# STM32F407VGT6TR_100P_MCU.net
KiCad netlist of a schematic drawn in Altium Designer
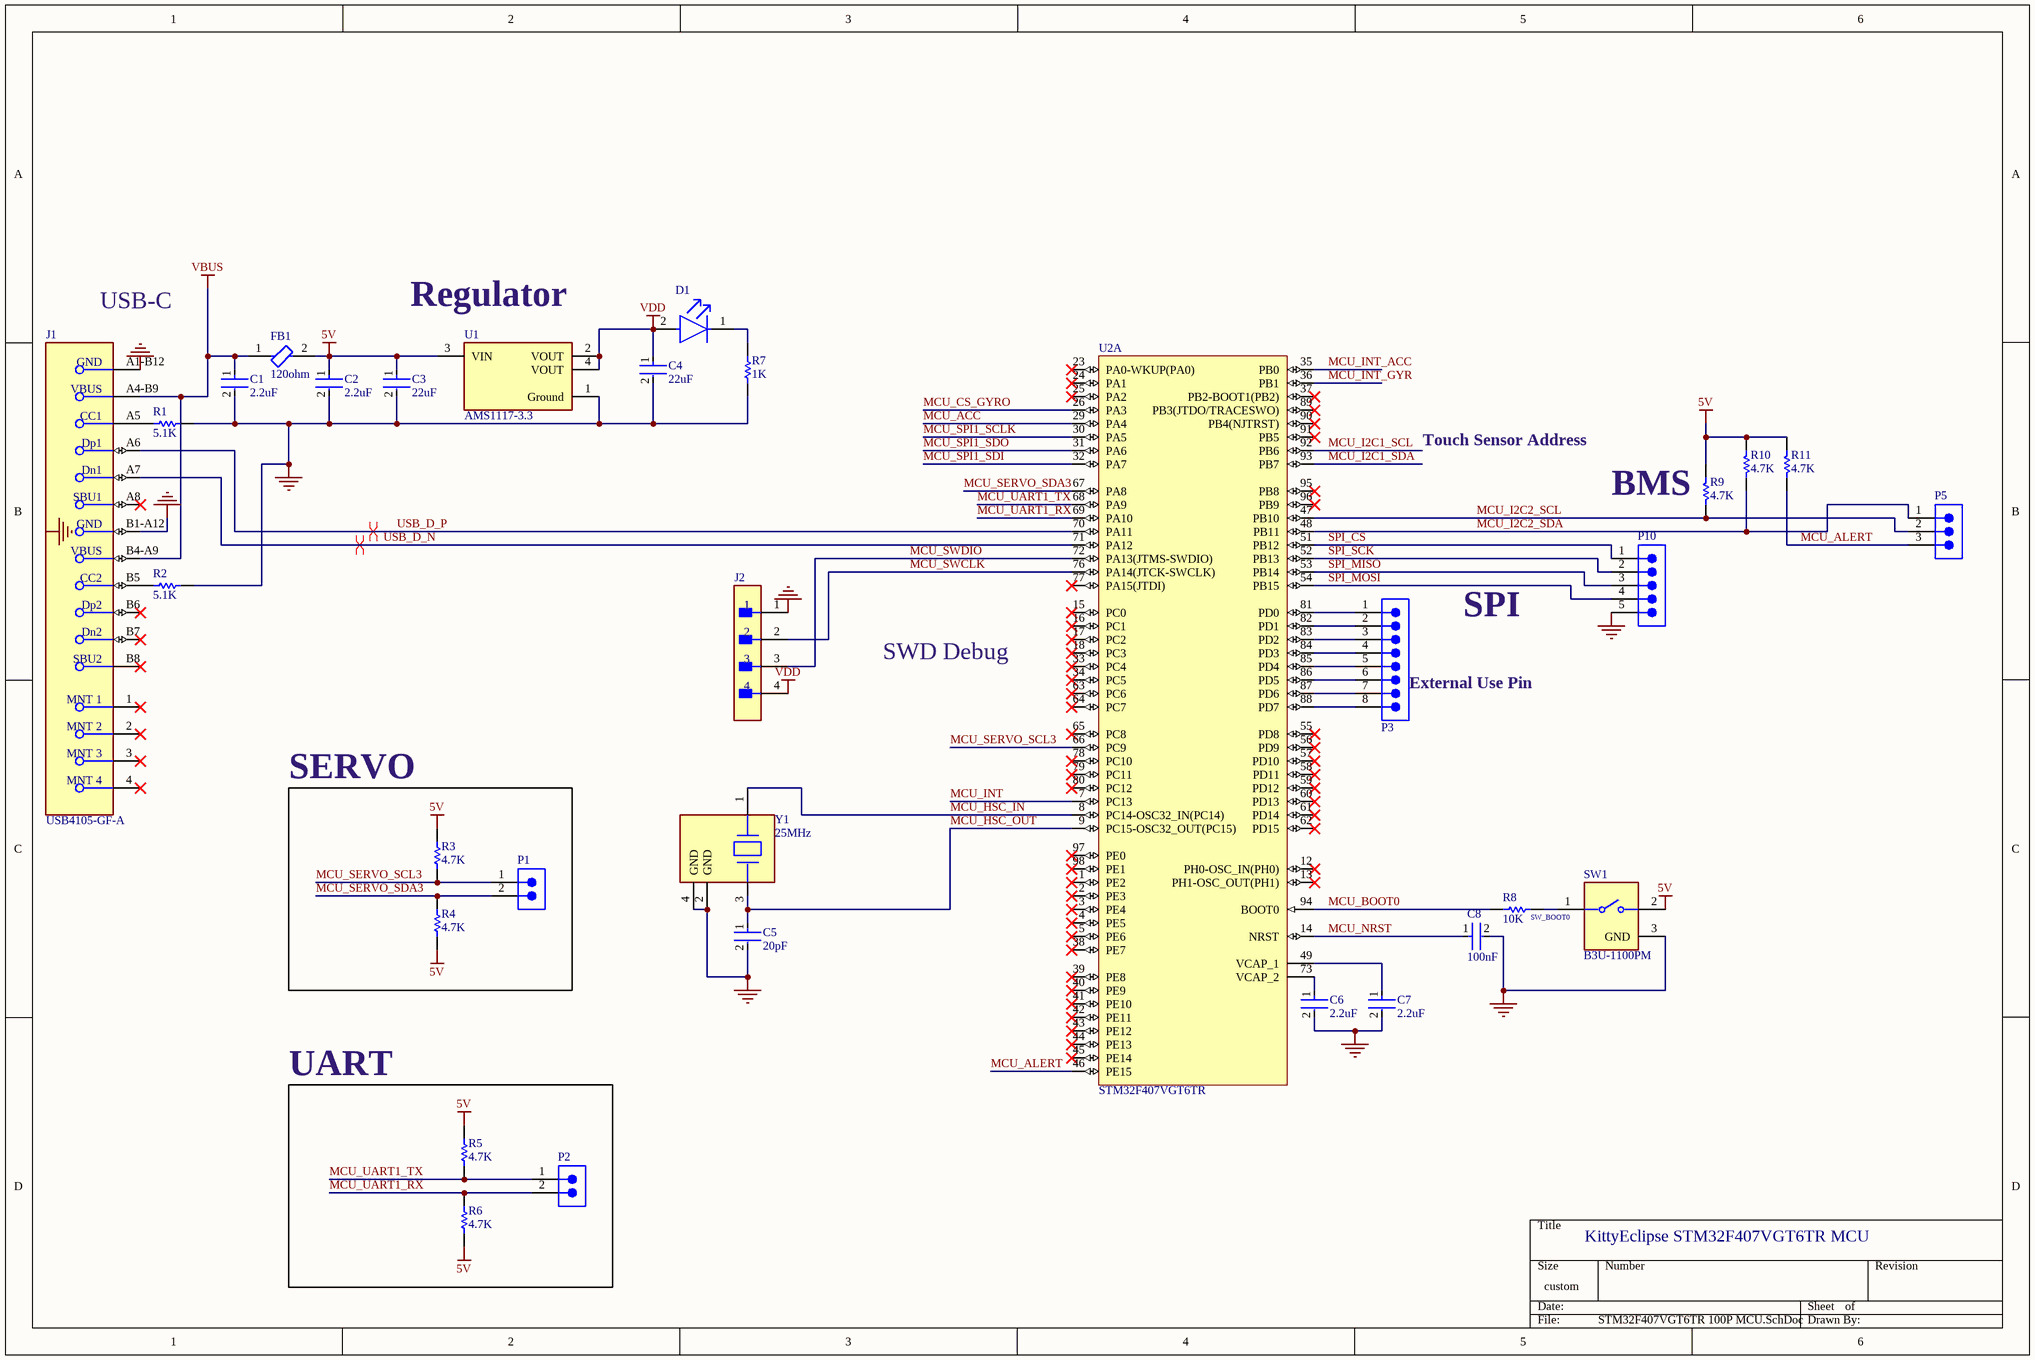
[diagram p0: STM32F407VGT6TR 100P MCU.SchDoc]

(export (version "E")
  (design (tool "Eeschema 10.0.6"))
  (components
    (comp (ref "C1")
      (value "2.2uF")
      (footprint "FP-CL10-IPC_A")
      (description "Cap Ceramic 2.2uF 16V X5R ±10% Pad SMD 0603 +85°C T/R")
      (fields (field (name "TOLERANCE") "10%") (field (name "VOLTAGE") "16V"))
      (libsource (lib "Altium Content Vault") (part "b4654b650e69147ec39a6b967a45e02"))
    )
    (comp (ref "C2")
      (value "2.2uF")
      (footprint "FP-CL10-IPC_A")
      (description "Cap Ceramic 2.2uF 16V X5R ±10% Pad SMD 0603 +85°C T/R")
      (fields (field (name "TOLERANCE") "10%") (field (name "VOLTAGE") "16V"))
      (libsource (lib "Altium Content Vault") (part "b4654b650e69147ec39a6b967a45e02"))
    )
    (comp (ref "C3")
      (value "22uF")
      (footprint "FP-CL21-IPC_A")
      (description "CL21 Series 0805 22uF 6.3V ±20% Tolerance X5R Multilayer Ceramic Chip Capacitor")
      (fields (field (name "TOLERANCE") "20%"))
      (libsource (lib "Altium Content Vault") (part "b4654b650e69147ec39a6b967a45e02"))
    )
    (comp (ref "C4")
      (value "22uF")
      (footprint "FP-CL21-IPC_A")
      (description "CL21 Series 0805 22uF 6.3V ±20% Tolerance X5R Multilayer Ceramic Chip Capacitor")
      (fields (field (name "TOLERANCE") "20%"))
      (libsource (lib "Altium Content Vault") (part "b4654b650e69147ec39a6b967a45e02"))
    )
    (comp (ref "C5")
      (value "20pF")
      (footprint "FP-GCM155-0_05-IPC_A")
      (description "Ceramic Capacitor for Automotive 220pF ±5% 50VDC C0G 0402 Paper T/R")
      (fields (field (name "VOLTAGE") "50V") (field (name "TOLERANCE") "5%"))
      (libsource (lib "Altium Content Vault") (part "02cd4be3c70576c341d710602a673aa"))
    )
    (comp (ref "C6")
      (value "2.2uF")
      (footprint "FP-CL10-IPC_A")
      (description "Cap Ceramic 2.2uF 16V X5R ±10% Pad SMD 0603 +85°C T/R")
      (fields (field (name "TOLERANCE") "10%") (field (name "VOLTAGE") "16V"))
      (libsource (lib "Altium Content Vault") (part "b4654b650e69147ec39a6b967a45e02"))
    )
    (comp (ref "C7")
      (value "2.2uF")
      (footprint "FP-CL10-IPC_A")
      (description "Cap Ceramic 2.2uF 16V X5R ±10% Pad SMD 0603 +85°C T/R")
      (fields (field (name "TOLERANCE") "10%") (field (name "VOLTAGE") "16V"))
      (libsource (lib "Altium Content Vault") (part "b4654b650e69147ec39a6b967a45e02"))
    )
    (comp (ref "C8")
      (value "100nF")
      (footprint "FP-CL93-IPC_C")
      (description "Cap Ceramic 100nF 10V X7R ±10% SMD 0402 +125°C Paper T/R")
      (libsource (lib "Altium Content Vault") (part "b4654b650e69147ec39a6b967a45e02"))
    )
    (comp (ref "D1")
      (value "LTST-C190GKT")
      (footprint "FP-LTST-C190GKT-MFG")
      (description "LED GREEN CLEAR CHIP SMD")
      (fields (field (name "VOLTAGE") "2V"))
      (libsource (lib "Altium Content Vault") (part "8706943c75ba83719d021d2fdc84c58"))
    )
    (comp (ref "FB1")
      (value "120ohm")
      (footprint "FP-MPZ1608-0_8-IPC_C")
      (description "Power line Ferrite Bead 390Ω @ 100MHz 1.2A DCR 0.12Ω SMD 0603")
      (fields (field (name "TOLERANCE") "25%"))
      (libsource (lib "Altium Content Vault") (part "5f30dd21d616792df468990f7003faa"))
    )
    (comp (ref "J1")
      (value "USB4105-GF-A")
      (footprint "FP-USB4105-GF-A-MFG")
      (description "CONN RCPT USB2.0 TYPEC 5A")
      (fields
        (field (name "MANUFACTURER") "GCT")
        (field (name "OCTOPART") "https://octopart.com/usb4105-gf-a-gct-106627878")
      )
      (libsource (lib "Altium Content Vault") (part "e7c17a616881a82b79941196b4bec10"))
    )
    (comp (ref "J2")
      (value "B4B-ZR(LF)(SN)")
      (footprint "FP-B4B-ZR_LF_SN-MFG")
      (description "CONN HEADER VERT 4POS 1.5MM")
      (libsource (lib "Altium Content Vault") (part "299a8cea1bdcbc3624fe62c390fa72c"))
    )
    (comp (ref "P1")
      (value "61300211121")
      (footprint "61300211121")
      (libsource (lib "Altium Content Vault") (part "Header_Male_1R_02P"))
    )
    (comp (ref "P2")
      (value "61300211121")
      (footprint "61300211121")
      (libsource (lib "Altium Content Vault") (part "Header_Male_1R_02P"))
    )
    (comp (ref "P3")
      (value "61300811121")
      (footprint "61300811121")
      (libsource (lib "Altium Content Vault") (part "Header_Male_1R_08P"))
    )
    (comp (ref "P5")
      (value "61300311121")
      (footprint "61300311121")
      (libsource (lib "Altium Content Vault") (part "Header_Male_1R_03P"))
    )
    (comp (ref "P10")
      (value "61300511121")
      (footprint "61300511121")
      (libsource (lib "Altium Content Vault") (part "Header_Male_1R_05P"))
    )
    (comp (ref "R1")
      (value "5.1K")
      (footprint "RESC1005X40X25NL10T10")
      (fields (field (name "MANUFACTURER") "Panasonic") (field (name "PART NUMBER") "ERA-2AEB512X"))
      (libsource (lib "Altium Content Vault") (part "RES"))
    )
    (comp (ref "R2")
      (value "5.1K")
      (footprint "RESC1005X40X25NL10T10")
      (fields (field (name "MANUFACTURER") "Panasonic") (field (name "PART NUMBER") "ERA-2AEB512X"))
      (libsource (lib "Altium Content Vault") (part "RES"))
    )
    (comp (ref "R3")
      (value "4.7K")
      (footprint "RESC1608X55X25LL10T15")
      (description "Chip Resistor, 4.7 KOhm, +/- 1%, 0.1 W, -55 to 155 degC, 0603 (1608 Metric), RoHS, Tape and Reel")
      (fields (field (name "MANUFACTURER") "Yageo") (field (name "TOLERANCE") "1%"))
      (libsource (lib "Altium Content Vault") (part "RES-2"))
    )
    (comp (ref "R4")
      (value "4.7K")
      (footprint "RESC1608X55X25LL10T15")
      (description "Chip Resistor, 4.7 KOhm, +/- 1%, 0.1 W, -55 to 155 degC, 0603 (1608 Metric), RoHS, Tape and Reel")
      (fields (field (name "MANUFACTURER") "Yageo") (field (name "TOLERANCE") "1%"))
      (libsource (lib "Altium Content Vault") (part "RES-2"))
    )
    (comp (ref "R5")
      (value "4.7K")
      (footprint "RESC1608X55X25LL10T15")
      (description "Chip Resistor, 4.7 KOhm, +/- 1%, 0.1 W, -55 to 155 degC, 0603 (1608 Metric), RoHS, Tape and Reel")
      (fields (field (name "MANUFACTURER") "Yageo") (field (name "TOLERANCE") "1%"))
      (libsource (lib "Altium Content Vault") (part "RES-2"))
    )
    (comp (ref "R6")
      (value "4.7K")
      (footprint "RESC1608X55X25LL10T15")
      (description "Chip Resistor, 4.7 KOhm, +/- 1%, 0.1 W, -55 to 155 degC, 0603 (1608 Metric), RoHS, Tape and Reel")
      (fields (field (name "MANUFACTURER") "Yageo") (field (name "TOLERANCE") "1%"))
      (libsource (lib "Altium Content Vault") (part "RES-2"))
    )
    (comp (ref "R7")
      (value "1K")
      (footprint "RESC1608X55X30LL15T15")
      (fields (field (name "PART NUMBER") "ERJ-3EKF1001V") (field (name "MANUFACTURER") "Panasonic"))
      (libsource (lib "Altium Content Vault") (part "RES"))
    )
    (comp (ref "R8")
      (value "10K")
      (footprint "RESC1608X55X25ML10T15")
      (description "Resistor, 10 KOhm, +/- 5%, 100 mW, -55 to 155 degC, 0603 (1608 Metric), RoHS, Tape and Reel")
      (fields (field (name "MANUFACTURER") "Yageo") (field (name "TOLERANCE") "5%"))
      (libsource (lib "Altium Content Vault") (part "RES-2"))
    )
    (comp (ref "R9")
      (value "4.7K")
      (footprint "RESC1608X55X25LL10T15")
      (description "Chip Resistor, 4.7 KOhm, +/- 1%, 0.1 W, -55 to 155 degC, 0603 (1608 Metric), RoHS, Tape and Reel")
      (fields (field (name "MANUFACTURER") "Yageo") (field (name "TOLERANCE") "1%"))
      (libsource (lib "Altium Content Vault") (part "RES-2"))
    )
    (comp (ref "R10")
      (value "4.7K")
      (footprint "RESC1608X55X25LL10T15")
      (description "Chip Resistor, 4.7 KOhm, +/- 1%, 0.1 W, -55 to 155 degC, 0603 (1608 Metric), RoHS, Tape and Reel")
      (fields (field (name "MANUFACTURER") "Yageo") (field (name "TOLERANCE") "1%"))
      (libsource (lib "Altium Content Vault") (part "RES-2"))
    )
    (comp (ref "R11")
      (value "4.7K")
      (footprint "RESC1608X55X25LL10T15")
      (description "Chip Resistor, 4.7 KOhm, +/- 1%, 0.1 W, -55 to 155 degC, 0603 (1608 Metric), RoHS, Tape and Reel")
      (fields (field (name "MANUFACTURER") "Yageo") (field (name "TOLERANCE") "1%"))
      (libsource (lib "Altium Content Vault") (part "RES-2"))
    )
    (comp (ref "SW1")
      (value "B3U-1100PM")
      (footprint "FP-B3U-1100PM-MFG")
      (description "SWITCH TACTILE SPST-NO 0.05A 12V")
      (libsource (lib "Altium Content Vault") (part "6d7322ea62e06c21cb959ab9578dfa0"))
    )
    (comp (ref "U1")
      (value "AMS1117-3.3")
      (footprint "FP-AMS1117-IPC_C")
      (description "LDO Voltage Regulators 1A, 3.3V")
      (fields
        (field (name "OCTOPART") "https://octopart.com/ams1117-3.3-advanced+monolithic+systems-25899300")
        (field (name "MANUFACTURER") "Advanced Monolithic Systems")
      )
      (libsource (lib "Altium Content Vault") (part "8bdbb5f8e77002000e30dd2845d0354"))
    )
    (comp (ref "U2")
      (value "STM32F407VGT6TR")
      (footprint "STM-LQFP100_L")
      (fields (field (name "MANUFACTURER") "STMicroelectronics"))
      (libsource (lib "Altium Content Vault") (part "MC-ARM-STM32F40X_41X-SQ100"))
    )
    (comp (ref "Y1")
      (value "25MHz")
      (footprint "FP-ABM11W-MFG")
      (description "Crystal 25MHz ±10ppm 8pF SMD-4 2mm x 1.6mm")
      (libsource (lib "Altium Content Vault") (part "5fba445d8d5f95165d6b3865099b029"))
    )
  )
  (nets
    (net (code "1") (name "/MCU_ACC") (class "Default")
      (node (ref "U2") (pin "29") (pinfunction "PA4_29") (pintype "bidirectional"))
    )
    (net (code "2") (name "/MCU_ALERT") (class "Default")
      (node (ref "P5") (pin "3") (pinfunction "3_3") (pintype "passive"))
      (node (ref "R11") (pin "2") (pinfunction "2_2") (pintype "passive"))
      (node (ref "U2") (pin "46") (pinfunction "PE15_46") (pintype "bidirectional"))
    )
    (net (code "3") (name "/MCU_BOOT0") (class "Default")
      (node (ref "R8") (pin "1") (pinfunction "1_1") (pintype "passive"))
      (node (ref "U2") (pin "94") (pinfunction "BOOT0_94") (pintype "input"))
    )
    (net (code "4") (name "/MCU_CS_GYRO") (class "Default")
      (node (ref "U2") (pin "26") (pinfunction "PA3_26") (pintype "bidirectional"))
    )
    (net (code "5") (name "/MCU_HSC_IN") (class "Default")
      (node (ref "U2") (pin "8") (pinfunction "PC14-OSC32_IN(PC14)_8") (pintype "bidirectional"))
      (node (ref "Y1") (pin "1") (pinfunction "1_1") (pintype "passive"))
    )
    (net (code "6") (name "/MCU_HSC_OUT") (class "Default")
      (node (ref "C5") (pin "1") (pinfunction "1_1") (pintype "passive"))
      (node (ref "U2") (pin "9") (pinfunction "PC15-OSC32_OUT(PC15)_9") (pintype "bidirectional"))
      (node (ref "Y1") (pin "3") (pinfunction "3_3") (pintype "passive"))
    )
    (net (code "7") (name "/MCU_I2C1_SCL") (class "Default")
      (node (ref "U2") (pin "92") (pinfunction "PB6_92") (pintype "bidirectional"))
    )
    (net (code "8") (name "/MCU_I2C1_SDA") (class "Default")
      (node (ref "U2") (pin "93") (pinfunction "PB7_93") (pintype "bidirectional"))
    )
    (net (code "9") (name "/MCU_I2C2_SCL") (class "Default")
      (node (ref "P5") (pin "2") (pinfunction "2_2") (pintype "passive"))
      (node (ref "R9") (pin "2") (pinfunction "2_2") (pintype "passive"))
      (node (ref "U2") (pin "47") (pinfunction "PB10_47") (pintype "bidirectional"))
    )
    (net (code "10") (name "/MCU_I2C2_SDA") (class "Default")
      (node (ref "P5") (pin "1") (pinfunction "1_1") (pintype "passive"))
      (node (ref "R10") (pin "2") (pinfunction "2_2") (pintype "passive"))
      (node (ref "U2") (pin "48") (pinfunction "PB11_48") (pintype "bidirectional"))
    )
    (net (code "11") (name "/MCU_INT") (class "Default")
      (node (ref "U2") (pin "7") (pinfunction "PC13_7") (pintype "bidirectional"))
    )
    (net (code "12") (name "/MCU_INT_ACC") (class "Default")
      (node (ref "U2") (pin "35") (pinfunction "PB0_35") (pintype "bidirectional"))
    )
    (net (code "13") (name "/MCU_INT_GYR") (class "Default")
      (node (ref "U2") (pin "36") (pinfunction "PB1_36") (pintype "bidirectional"))
    )
    (net (code "14") (name "/MCU_NRST") (class "Default")
      (node (ref "C8") (pin "1") (pinfunction "1_1") (pintype "passive"))
      (node (ref "U2") (pin "14") (pinfunction "NRST_14") (pintype "bidirectional"))
    )
    (net (code "15") (name "/MCU_SERVO_SCL3") (class "Default")
      (node (ref "P1") (pin "1") (pinfunction "1_1") (pintype "passive"))
      (node (ref "R3") (pin "1") (pinfunction "1_1") (pintype "passive"))
      (node (ref "U2") (pin "66") (pinfunction "PC9_66") (pintype "bidirectional"))
    )
    (net (code "16") (name "/MCU_SERVO_SDA3") (class "Default")
      (node (ref "P1") (pin "2") (pinfunction "2_2") (pintype "passive"))
      (node (ref "R4") (pin "2") (pinfunction "2_2") (pintype "passive"))
      (node (ref "U2") (pin "67") (pinfunction "PA8_67") (pintype "bidirectional"))
    )
    (net (code "17") (name "/MCU_SPI1_SCLK") (class "Default")
      (node (ref "U2") (pin "30") (pinfunction "PA5_30") (pintype "bidirectional"))
    )
    (net (code "18") (name "/MCU_SPI1_SDI") (class "Default")
      (node (ref "U2") (pin "32") (pinfunction "PA7_32") (pintype "bidirectional"))
    )
    (net (code "19") (name "/MCU_SPI1_SDO") (class "Default")
      (node (ref "U2") (pin "31") (pinfunction "PA6_31") (pintype "bidirectional"))
    )
    (net (code "20") (name "/MCU_SWCLK") (class "Default")
      (node (ref "J2") (pin "2") (pinfunction "2_2") (pintype "passive"))
      (node (ref "U2") (pin "76") (pinfunction "PA14(JTCK-SWCLK)_76") (pintype "bidirectional"))
    )
    (net (code "21") (name "/MCU_SWDIO") (class "Default")
      (node (ref "J2") (pin "3") (pinfunction "3_3") (pintype "passive"))
      (node (ref "U2") (pin "72") (pinfunction "PA13(JTMS-SWDIO)_72") (pintype "bidirectional"))
    )
    (net (code "22") (name "/MCU_UART1_RX") (class "Default")
      (node (ref "P2") (pin "2") (pinfunction "2_2") (pintype "passive"))
      (node (ref "R6") (pin "2") (pinfunction "2_2") (pintype "passive"))
      (node (ref "U2") (pin "69") (pinfunction "PA10_69") (pintype "bidirectional"))
    )
    (net (code "23") (name "/MCU_UART1_TX") (class "Default")
      (node (ref "P2") (pin "1") (pinfunction "1_1") (pintype "passive"))
      (node (ref "R5") (pin "2") (pinfunction "2_2") (pintype "passive"))
      (node (ref "U2") (pin "68") (pinfunction "PA9_68") (pintype "bidirectional"))
    )
    (net (code "24") (name "/SPI_CS") (class "Default")
      (node (ref "P10") (pin "1") (pinfunction "1_1") (pintype "passive"))
      (node (ref "U2") (pin "51") (pinfunction "PB12_51") (pintype "bidirectional"))
    )
    (net (code "25") (name "/SPI_MISO") (class "Default")
      (node (ref "P10") (pin "3") (pinfunction "3_3") (pintype "passive"))
      (node (ref "U2") (pin "53") (pinfunction "PB14_53") (pintype "bidirectional"))
    )
    (net (code "26") (name "/SPI_MOSI") (class "Default")
      (node (ref "P10") (pin "4") (pinfunction "4_4") (pintype "passive"))
      (node (ref "U2") (pin "54") (pinfunction "PB15_54") (pintype "bidirectional"))
    )
    (net (code "27") (name "/SPI_SCK") (class "Default")
      (node (ref "P10") (pin "2") (pinfunction "2_2") (pintype "passive"))
      (node (ref "U2") (pin "52") (pinfunction "PB13_52") (pintype "bidirectional"))
    )
    (net (code "28") (name "/USB_D_N") (class "Default")
      (node (ref "J1") (pin "A7") (pinfunction "Dn1_A7") (pintype "bidirectional"))
      (node (ref "U2") (pin "71") (pinfunction "PA12_71") (pintype "bidirectional"))
    )
    (net (code "29") (name "/USB_D_P") (class "Default")
      (node (ref "J1") (pin "A6") (pinfunction "Dp1_A6") (pintype "bidirectional"))
      (node (ref "U2") (pin "70") (pinfunction "PA11_70") (pintype "bidirectional"))
    )
    (net (code "30") (name "5V") (class "Default")
      (node (ref "C2") (pin "1") (pinfunction "1_1") (pintype "passive"))
      (node (ref "C3") (pin "1") (pinfunction "1_1") (pintype "passive"))
      (node (ref "FB1") (pin "2") (pinfunction "2_2") (pintype "passive"))
      (node (ref "R10") (pin "1") (pinfunction "1_1") (pintype "passive"))
      (node (ref "R11") (pin "1") (pinfunction "1_1") (pintype "passive"))
      (node (ref "R3") (pin "2") (pinfunction "2_2") (pintype "passive"))
      (node (ref "R4") (pin "1") (pinfunction "1_1") (pintype "passive"))
      (node (ref "R5") (pin "1") (pinfunction "1_1") (pintype "passive"))
      (node (ref "R6") (pin "1") (pinfunction "1_1") (pintype "passive"))
      (node (ref "R9") (pin "1") (pinfunction "1_1") (pintype "passive"))
      (node (ref "SW1") (pin "2") (pinfunction "2_2") (pintype "passive"))
      (node (ref "U1") (pin "3") (pinfunction "VIN_3") (pintype "power_in"))
    )
    (net (code "31") (name "GND") (class "Default")
      (node (ref "C1") (pin "2") (pinfunction "2_2") (pintype "passive"))
      (node (ref "C2") (pin "2") (pinfunction "2_2") (pintype "passive"))
      (node (ref "C3") (pin "2") (pinfunction "2_2") (pintype "passive"))
      (node (ref "C4") (pin "2") (pinfunction "2_2") (pintype "passive"))
      (node (ref "C5") (pin "2") (pinfunction "2_2") (pintype "passive"))
      (node (ref "C6") (pin "2") (pinfunction "2_2") (pintype "passive"))
      (node (ref "C7") (pin "2") (pinfunction "2_2") (pintype "passive"))
      (node (ref "C8") (pin "2") (pinfunction "2_2") (pintype "passive"))
      (node (ref "J1") (pin "A1-B12") (pinfunction "GND_A1-B12") (pintype "power_in"))
      (node (ref "J1") (pin "B1-A12") (pinfunction "GND_B1-A12") (pintype "bidirectional"))
      (node (ref "J2") (pin "1") (pinfunction "1_1") (pintype "passive"))
      (node (ref "P10") (pin "5") (pinfunction "5_5") (pintype "passive"))
      (node (ref "R1") (pin "2") (pinfunction "2_2") (pintype "passive"))
      (node (ref "R2") (pin "2") (pinfunction "2_2") (pintype "passive"))
      (node (ref "R7") (pin "2") (pinfunction "2_2") (pintype "passive"))
      (node (ref "SW1") (pin "3") (pinfunction "GND_3") (pintype "power_in"))
      (node (ref "U1") (pin "1") (pinfunction "Ground_1") (pintype "power_in"))
      (node (ref "Y1") (pin "2") (pinfunction "GND_2") (pintype "power_in"))
      (node (ref "Y1") (pin "4") (pinfunction "GND_4") (pintype "power_in"))
    )
    (net (code "32") (name "Net-(D1-C)") (class "Default")
      (node (ref "D1") (pin "1") (pinfunction "C_1") (pintype "passive"))
      (node (ref "R7") (pin "1") (pinfunction "1_1") (pintype "passive"))
    )
    (net (code "33") (name "Net-(J1-CC1)") (class "Default")
      (node (ref "J1") (pin "A5") (pinfunction "CC1_A5") (pintype "power_in"))
      (node (ref "R1") (pin "1") (pinfunction "1_1") (pintype "passive"))
    )
    (net (code "34") (name "Net-(J1-CC2)") (class "Default")
      (node (ref "J1") (pin "B5") (pinfunction "CC2_B5") (pintype "bidirectional"))
      (node (ref "R2") (pin "1") (pinfunction "1_1") (pintype "passive"))
    )
    (net (code "35") (name "Net-(R8-Pad2)") (class "Default")
      (node (ref "R8") (pin "2") (pinfunction "2_2") (pintype "passive"))
      (node (ref "SW1") (pin "1") (pinfunction "1_1") (pintype "passive"))
    )
    (net (code "36") (name "Net-(U2A-PD0)") (class "Default")
      (node (ref "P3") (pin "1") (pinfunction "1_1") (pintype "passive"))
      (node (ref "U2") (pin "81") (pinfunction "PD0_81") (pintype "bidirectional"))
    )
    (net (code "37") (name "Net-(U2A-PD1)") (class "Default")
      (node (ref "P3") (pin "2") (pinfunction "2_2") (pintype "passive"))
      (node (ref "U2") (pin "82") (pinfunction "PD1_82") (pintype "bidirectional"))
    )
    (net (code "38") (name "Net-(U2A-PD2)") (class "Default")
      (node (ref "P3") (pin "3") (pinfunction "3_3") (pintype "passive"))
      (node (ref "U2") (pin "83") (pinfunction "PD2_83") (pintype "bidirectional"))
    )
    (net (code "39") (name "Net-(U2A-PD3)") (class "Default")
      (node (ref "P3") (pin "4") (pinfunction "4_4") (pintype "passive"))
      (node (ref "U2") (pin "84") (pinfunction "PD3_84") (pintype "bidirectional"))
    )
    (net (code "40") (name "Net-(U2A-PD4)") (class "Default")
      (node (ref "P3") (pin "5") (pinfunction "5_5") (pintype "passive"))
      (node (ref "U2") (pin "85") (pinfunction "PD4_85") (pintype "bidirectional"))
    )
    (net (code "41") (name "Net-(U2A-PD5)") (class "Default")
      (node (ref "P3") (pin "6") (pinfunction "6_6") (pintype "passive"))
      (node (ref "U2") (pin "86") (pinfunction "PD5_86") (pintype "bidirectional"))
    )
    (net (code "42") (name "Net-(U2A-PD6)") (class "Default")
      (node (ref "P3") (pin "7") (pinfunction "7_7") (pintype "passive"))
      (node (ref "U2") (pin "87") (pinfunction "PD6_87") (pintype "bidirectional"))
    )
    (net (code "43") (name "Net-(U2A-PD7)") (class "Default")
      (node (ref "P3") (pin "8") (pinfunction "8_8") (pintype "passive"))
      (node (ref "U2") (pin "88") (pinfunction "PD7_88") (pintype "bidirectional"))
    )
    (net (code "44") (name "Net-(U2A-VCAP_1)") (class "Default")
      (node (ref "C7") (pin "1") (pinfunction "1_1") (pintype "passive"))
      (node (ref "U2") (pin "49") (pinfunction "VCAP_1_49") (pintype "power_in"))
    )
    (net (code "45") (name "Net-(U2A-VCAP_2)") (class "Default")
      (node (ref "C6") (pin "1") (pinfunction "1_1") (pintype "passive"))
      (node (ref "U2") (pin "73") (pinfunction "VCAP_2_73") (pintype "power_in"))
    )
    (net (code "46") (name "VBUS") (class "Default")
      (node (ref "C1") (pin "1") (pinfunction "1_1") (pintype "passive"))
      (node (ref "FB1") (pin "1") (pinfunction "1_1") (pintype "passive"))
      (node (ref "J1") (pin "A4-B9") (pinfunction "VBUS_A4-B9") (pintype "power_in"))
      (node (ref "J1") (pin "B4-A9") (pinfunction "VBUS_B4-A9") (pintype "bidirectional"))
    )
    (net (code "47") (name "VDD") (class "Default")
      (node (ref "C4") (pin "1") (pinfunction "1_1") (pintype "passive"))
      (node (ref "D1") (pin "2") (pinfunction "A_2") (pintype "passive"))
      (node (ref "J2") (pin "4") (pinfunction "4_4") (pintype "passive"))
      (node (ref "U1") (pin "2") (pinfunction "VOUT_2") (pintype "passive"))
      (node (ref "U1") (pin "4") (pinfunction "VOUT_4") (pintype "passive"))
    )
    (net (code "48") (name "unconnected-(J1-Dn2-PadB7)") (class "Default")
      (node (ref "J1") (pin "B7") (pinfunction "Dn2_B7") (pintype "bidirectional+no_connect"))
    )
    (net (code "49") (name "unconnected-(J1-Dp2-PadB6)") (class "Default")
      (node (ref "J1") (pin "B6") (pinfunction "Dp2_B6") (pintype "bidirectional+no_connect"))
    )
    (net (code "50") (name "unconnected-(J1-MNT_1-Pad1)") (class "Default")
      (node (ref "J1") (pin "1") (pinfunction "MNT_1_1") (pintype "power_in+no_connect"))
    )
    (net (code "51") (name "unconnected-(J1-MNT_2-Pad2)") (class "Default")
      (node (ref "J1") (pin "2") (pinfunction "MNT_2_2") (pintype "power_in+no_connect"))
    )
    (net (code "52") (name "unconnected-(J1-MNT_3-Pad3)") (class "Default")
      (node (ref "J1") (pin "3") (pinfunction "MNT_3_3") (pintype "power_in+no_connect"))
    )
    (net (code "53") (name "unconnected-(J1-MNT_4-Pad4)") (class "Default")
      (node (ref "J1") (pin "4") (pinfunction "MNT_4_4") (pintype "power_in+no_connect"))
    )
    (net (code "54") (name "unconnected-(J1-SBU1-PadA8)") (class "Default")
      (node (ref "J1") (pin "A8") (pinfunction "SBU1_A8") (pintype "bidirectional+no_connect"))
    )
    (net (code "55") (name "unconnected-(J1-SBU2-PadB8)") (class "Default")
      (node (ref "J1") (pin "B8") (pinfunction "SBU2_B8") (pintype "power_in+no_connect"))
    )
    (net (code "56") (name "unconnected-(U2A-PA0-WKUP(PA0)-Pad23)") (class "Default")
      (node (ref "U2") (pin "23") (pinfunction "PA0-WKUP(PA0)_23") (pintype "bidirectional+no_connect"))
    )
    (net (code "57") (name "unconnected-(U2A-PA1-Pad24)") (class "Default")
      (node (ref "U2") (pin "24") (pinfunction "PA1_24") (pintype "bidirectional+no_connect"))
    )
    (net (code "58") (name "unconnected-(U2A-PA2-Pad25)") (class "Default")
      (node (ref "U2") (pin "25") (pinfunction "PA2_25") (pintype "bidirectional+no_connect"))
    )
    (net (code "59") (name "unconnected-(U2A-PA15(JTDI)-Pad77)") (class "Default")
      (node (ref "U2") (pin "77") (pinfunction "PA15(JTDI)_77") (pintype "bidirectional+no_connect"))
    )
    (net (code "60") (name "unconnected-(U2A-PB2-BOOT1(PB2)-Pad37)") (class "Default")
      (node (ref "U2") (pin "37") (pinfunction "PB2-BOOT1(PB2)_37") (pintype "bidirectional+no_connect"))
    )
    (net (code "61") (name "unconnected-(U2A-PB3(JTDO{slash}TRACESWO)-Pad89)") (class "Default")
      (node (ref "U2") (pin "89") (pinfunction "PB3(JTDO/TRACESWO)_89") (pintype "bidirectional+no_connect"))
    )
    (net (code "62") (name "unconnected-(U2A-PB4(NJTRST)-Pad90)") (class "Default")
      (node (ref "U2") (pin "90") (pinfunction "PB4(NJTRST)_90") (pintype "bidirectional+no_connect"))
    )
    (net (code "63") (name "unconnected-(U2A-PB5-Pad91)") (class "Default")
      (node (ref "U2") (pin "91") (pinfunction "PB5_91") (pintype "bidirectional+no_connect"))
    )
    (net (code "64") (name "unconnected-(U2A-PB8-Pad95)") (class "Default")
      (node (ref "U2") (pin "95") (pinfunction "PB8_95") (pintype "bidirectional+no_connect"))
    )
    (net (code "65") (name "unconnected-(U2A-PB9-Pad96)") (class "Default")
      (node (ref "U2") (pin "96") (pinfunction "PB9_96") (pintype "bidirectional+no_connect"))
    )
    (net (code "66") (name "unconnected-(U2A-PC0-Pad15)") (class "Default")
      (node (ref "U2") (pin "15") (pinfunction "PC0_15") (pintype "bidirectional+no_connect"))
    )
    (net (code "67") (name "unconnected-(U2A-PC1-Pad16)") (class "Default")
      (node (ref "U2") (pin "16") (pinfunction "PC1_16") (pintype "bidirectional+no_connect"))
    )
    (net (code "68") (name "unconnected-(U2A-PC2-Pad17)") (class "Default")
      (node (ref "U2") (pin "17") (pinfunction "PC2_17") (pintype "bidirectional+no_connect"))
    )
    (net (code "69") (name "unconnected-(U2A-PC3-Pad18)") (class "Default")
      (node (ref "U2") (pin "18") (pinfunction "PC3_18") (pintype "bidirectional+no_connect"))
    )
    (net (code "70") (name "unconnected-(U2A-PC4-Pad33)") (class "Default")
      (node (ref "U2") (pin "33") (pinfunction "PC4_33") (pintype "bidirectional+no_connect"))
    )
    (net (code "71") (name "unconnected-(U2A-PC5-Pad34)") (class "Default")
      (node (ref "U2") (pin "34") (pinfunction "PC5_34") (pintype "bidirectional+no_connect"))
    )
    (net (code "72") (name "unconnected-(U2A-PC6-Pad63)") (class "Default")
      (node (ref "U2") (pin "63") (pinfunction "PC6_63") (pintype "bidirectional+no_connect"))
    )
    (net (code "73") (name "unconnected-(U2A-PC7-Pad64)") (class "Default")
      (node (ref "U2") (pin "64") (pinfunction "PC7_64") (pintype "bidirectional+no_connect"))
    )
    (net (code "74") (name "unconnected-(U2A-PC8-Pad65)") (class "Default")
      (node (ref "U2") (pin "65") (pinfunction "PC8_65") (pintype "bidirectional+no_connect"))
    )
    (net (code "75") (name "unconnected-(U2A-PC10-Pad78)") (class "Default")
      (node (ref "U2") (pin "78") (pinfunction "PC10_78") (pintype "bidirectional+no_connect"))
    )
    (net (code "76") (name "unconnected-(U2A-PC11-Pad79)") (class "Default")
      (node (ref "U2") (pin "79") (pinfunction "PC11_79") (pintype "bidirectional+no_connect"))
    )
    (net (code "77") (name "unconnected-(U2A-PC12-Pad80)") (class "Default")
      (node (ref "U2") (pin "80") (pinfunction "PC12_80") (pintype "bidirectional+no_connect"))
    )
    (net (code "78") (name "unconnected-(U2A-PD8-Pad55)") (class "Default")
      (node (ref "U2") (pin "55") (pinfunction "PD8_55") (pintype "bidirectional+no_connect"))
    )
    (net (code "79") (name "unconnected-(U2A-PD9-Pad56)") (class "Default")
      (node (ref "U2") (pin "56") (pinfunction "PD9_56") (pintype "bidirectional+no_connect"))
    )
    (net (code "80") (name "unconnected-(U2A-PD10-Pad57)") (class "Default")
      (node (ref "U2") (pin "57") (pinfunction "PD10_57") (pintype "bidirectional+no_connect"))
    )
    (net (code "81") (name "unconnected-(U2A-PD11-Pad58)") (class "Default")
      (node (ref "U2") (pin "58") (pinfunction "PD11_58") (pintype "bidirectional+no_connect"))
    )
    (net (code "82") (name "unconnected-(U2A-PD12-Pad59)") (class "Default")
      (node (ref "U2") (pin "59") (pinfunction "PD12_59") (pintype "bidirectional+no_connect"))
    )
    (net (code "83") (name "unconnected-(U2A-PD13-Pad60)") (class "Default")
      (node (ref "U2") (pin "60") (pinfunction "PD13_60") (pintype "bidirectional+no_connect"))
    )
    (net (code "84") (name "unconnected-(U2A-PD14-Pad61)") (class "Default")
      (node (ref "U2") (pin "61") (pinfunction "PD14_61") (pintype "bidirectional+no_connect"))
    )
    (net (code "85") (name "unconnected-(U2A-PD15-Pad62)") (class "Default")
      (node (ref "U2") (pin "62") (pinfunction "PD15_62") (pintype "bidirectional+no_connect"))
    )
    (net (code "86") (name "unconnected-(U2A-PE0-Pad97)") (class "Default")
      (node (ref "U2") (pin "97") (pinfunction "PE0_97") (pintype "bidirectional+no_connect"))
    )
    (net (code "87") (name "unconnected-(U2A-PE1-Pad98)") (class "Default")
      (node (ref "U2") (pin "98") (pinfunction "PE1_98") (pintype "bidirectional+no_connect"))
    )
    (net (code "88") (name "unconnected-(U2A-PE2-Pad1)") (class "Default")
      (node (ref "U2") (pin "1") (pinfunction "PE2_1") (pintype "bidirectional+no_connect"))
    )
    (net (code "89") (name "unconnected-(U2A-PE3-Pad2)") (class "Default")
      (node (ref "U2") (pin "2") (pinfunction "PE3_2") (pintype "bidirectional+no_connect"))
    )
    (net (code "90") (name "unconnected-(U2A-PE4-Pad3)") (class "Default")
      (node (ref "U2") (pin "3") (pinfunction "PE4_3") (pintype "bidirectional+no_connect"))
    )
    (net (code "91") (name "unconnected-(U2A-PE5-Pad4)") (class "Default")
      (node (ref "U2") (pin "4") (pinfunction "PE5_4") (pintype "bidirectional+no_connect"))
    )
    (net (code "92") (name "unconnected-(U2A-PE6-Pad5)") (class "Default")
      (node (ref "U2") (pin "5") (pinfunction "PE6_5") (pintype "bidirectional+no_connect"))
    )
    (net (code "93") (name "unconnected-(U2A-PE7-Pad38)") (class "Default")
      (node (ref "U2") (pin "38") (pinfunction "PE7_38") (pintype "bidirectional+no_connect"))
    )
    (net (code "94") (name "unconnected-(U2A-PE8-Pad39)") (class "Default")
      (node (ref "U2") (pin "39") (pinfunction "PE8_39") (pintype "bidirectional+no_connect"))
    )
    (net (code "95") (name "unconnected-(U2A-PE9-Pad40)") (class "Default")
      (node (ref "U2") (pin "40") (pinfunction "PE9_40") (pintype "bidirectional+no_connect"))
    )
    (net (code "96") (name "unconnected-(U2A-PE10-Pad41)") (class "Default")
      (node (ref "U2") (pin "41") (pinfunction "PE10_41") (pintype "bidirectional+no_connect"))
    )
    (net (code "97") (name "unconnected-(U2A-PE11-Pad42)") (class "Default")
      (node (ref "U2") (pin "42") (pinfunction "PE11_42") (pintype "bidirectional+no_connect"))
    )
    (net (code "98") (name "unconnected-(U2A-PE12-Pad43)") (class "Default")
      (node (ref "U2") (pin "43") (pinfunction "PE12_43") (pintype "bidirectional+no_connect"))
    )
    (net (code "99") (name "unconnected-(U2A-PE13-Pad44)") (class "Default")
      (node (ref "U2") (pin "44") (pinfunction "PE13_44") (pintype "bidirectional+no_connect"))
    )
    (net (code "100") (name "unconnected-(U2A-PE14-Pad45)") (class "Default")
      (node (ref "U2") (pin "45") (pinfunction "PE14_45") (pintype "bidirectional+no_connect"))
    )
    (net (code "101") (name "unconnected-(U2A-PH0-OSC_IN(PH0)-Pad12)") (class "Default")
      (node (ref "U2") (pin "12") (pinfunction "PH0-OSC_IN(PH0)_12") (pintype "bidirectional+no_connect"))
    )
    (net (code "102") (name "unconnected-(U2A-PH1-OSC_OUT(PH1)-Pad13)") (class "Default")
      (node (ref "U2") (pin "13") (pinfunction "PH1-OSC_OUT(PH1)_13") (pintype "bidirectional+no_connect"))
    )
  )
)
